# Accel.net
KiCad netlist of a schematic drawn in Altium Designer
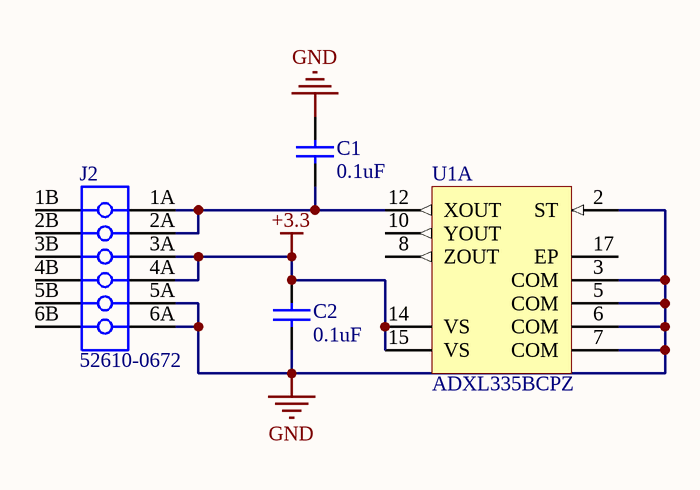
[diagram p0: Accel.SchDoc]

(export (version "E")
  (design (tool "Eeschema 10.0.6"))
  (components
    (comp (ref "C1")
      (value "0.1uF")
      (footprint "CAPC3216X127X50NL20T25")
      (description "CAP CER 0.1UF 100V 5% X7R 1206")
      (fields (field (name "MANUFACTURER PART NUMBER") "12061C104JAT2A"))
      (libsource (lib "CommunityVault") (part "CMP-126765-1"))
    )
    (comp (ref "C2")
      (value "0.1uF")
      (footprint "CAPC3216X127X50NL20T25")
      (description "CAP CER 0.1UF 100V 5% X7R 1206")
      (fields (field (name "MANUFACTURER PART NUMBER") "12061C104JAT2A"))
      (libsource (lib "CommunityVault") (part "CMP-126765-1"))
    )
    (comp (ref "J2")
      (value "52610-0672")
      (footprint "MOLX-52610-0672")
      (libsource (lib "CommunityVault") (part "MOLX-52610-0672"))
    )
    (comp (ref "U1")
      (value "ADXL335BCPZ")
      (footprint "ADI-CP-16-14_M")
      (libsource (lib "CommunityVault") (part "ADI-ADXL3XX-CP-16-XX"))
    )
  )
  (nets
    (net (code "1") (name "+3.3") (class "Default")
      (node (ref "C2") (pin "2") (pinfunction "2_2") (pintype "passive"))
      (node (ref "J2") (pin "3A") (pinfunction "3A_3A") (pintype "passive"))
      (node (ref "J2") (pin "4A") (pinfunction "4A_4A") (pintype "passive"))
      (node (ref "U1") (pin "14") (pinfunction "VS_14") (pintype "power_in"))
      (node (ref "U1") (pin "15") (pinfunction "VS_15") (pintype "power_in"))
    )
    (net (code "2") (name "GND") (class "Default")
      (node (ref "C1") (pin "2") (pinfunction "2_2") (pintype "passive"))
      (node (ref "C2") (pin "1") (pinfunction "1_1") (pintype "passive"))
      (node (ref "J2") (pin "5A") (pinfunction "5A_5A") (pintype "passive"))
      (node (ref "J2") (pin "6A") (pinfunction "6A_6A") (pintype "passive"))
      (node (ref "U1") (pin "2") (pinfunction "ST_2") (pintype "input"))
      (node (ref "U1") (pin "3") (pinfunction "COM_3") (pintype "power_in"))
      (node (ref "U1") (pin "5") (pinfunction "COM_5") (pintype "power_in"))
      (node (ref "U1") (pin "6") (pinfunction "COM_6") (pintype "power_in"))
      (node (ref "U1") (pin "7") (pinfunction "COM_7") (pintype "power_in"))
    )
    (net (code "3") (name "Net-(U1A-XOUT)") (class "Default")
      (node (ref "C1") (pin "1") (pinfunction "1_1") (pintype "passive"))
      (node (ref "J2") (pin "1A") (pinfunction "1A_1A") (pintype "passive"))
      (node (ref "J2") (pin "2A") (pinfunction "2A_2A") (pintype "passive"))
      (node (ref "U1") (pin "12") (pinfunction "XOUT_12") (pintype "output"))
    )
    (net (code "4") (name "unconnected-(J2-Pad1B)") (class "Default")
      (node (ref "J2") (pin "1B") (pinfunction "1B_1B") (pintype "passive"))
    )
    (net (code "5") (name "unconnected-(J2-Pad2B)") (class "Default")
      (node (ref "J2") (pin "2B") (pinfunction "2B_2B") (pintype "passive"))
    )
    (net (code "6") (name "unconnected-(J2-Pad3B)") (class "Default")
      (node (ref "J2") (pin "3B") (pinfunction "3B_3B") (pintype "passive"))
    )
    (net (code "7") (name "unconnected-(J2-Pad4B)") (class "Default")
      (node (ref "J2") (pin "4B") (pinfunction "4B_4B") (pintype "passive"))
    )
    (net (code "8") (name "unconnected-(J2-Pad5B)") (class "Default")
      (node (ref "J2") (pin "5B") (pinfunction "5B_5B") (pintype "passive"))
    )
    (net (code "9") (name "unconnected-(J2-Pad6B)") (class "Default")
      (node (ref "J2") (pin "6B") (pinfunction "6B_6B") (pintype "passive"))
    )
    (net (code "10") (name "unconnected-(U1A-EP-Pad17)") (class "Default")
      (node (ref "U1") (pin "17") (pinfunction "EP_17") (pintype "passive"))
    )
    (net (code "11") (name "unconnected-(U1A-YOUT-Pad10)") (class "Default")
      (node (ref "U1") (pin "10") (pinfunction "YOUT_10") (pintype "output"))
    )
    (net (code "12") (name "unconnected-(U1A-ZOUT-Pad8)") (class "Default")
      (node (ref "U1") (pin "8") (pinfunction "ZOUT_8") (pintype "output"))
    )
  )
)
